# Diver_Board_V1_0.net
KiCad netlist of a schematic drawn in Altium Designer
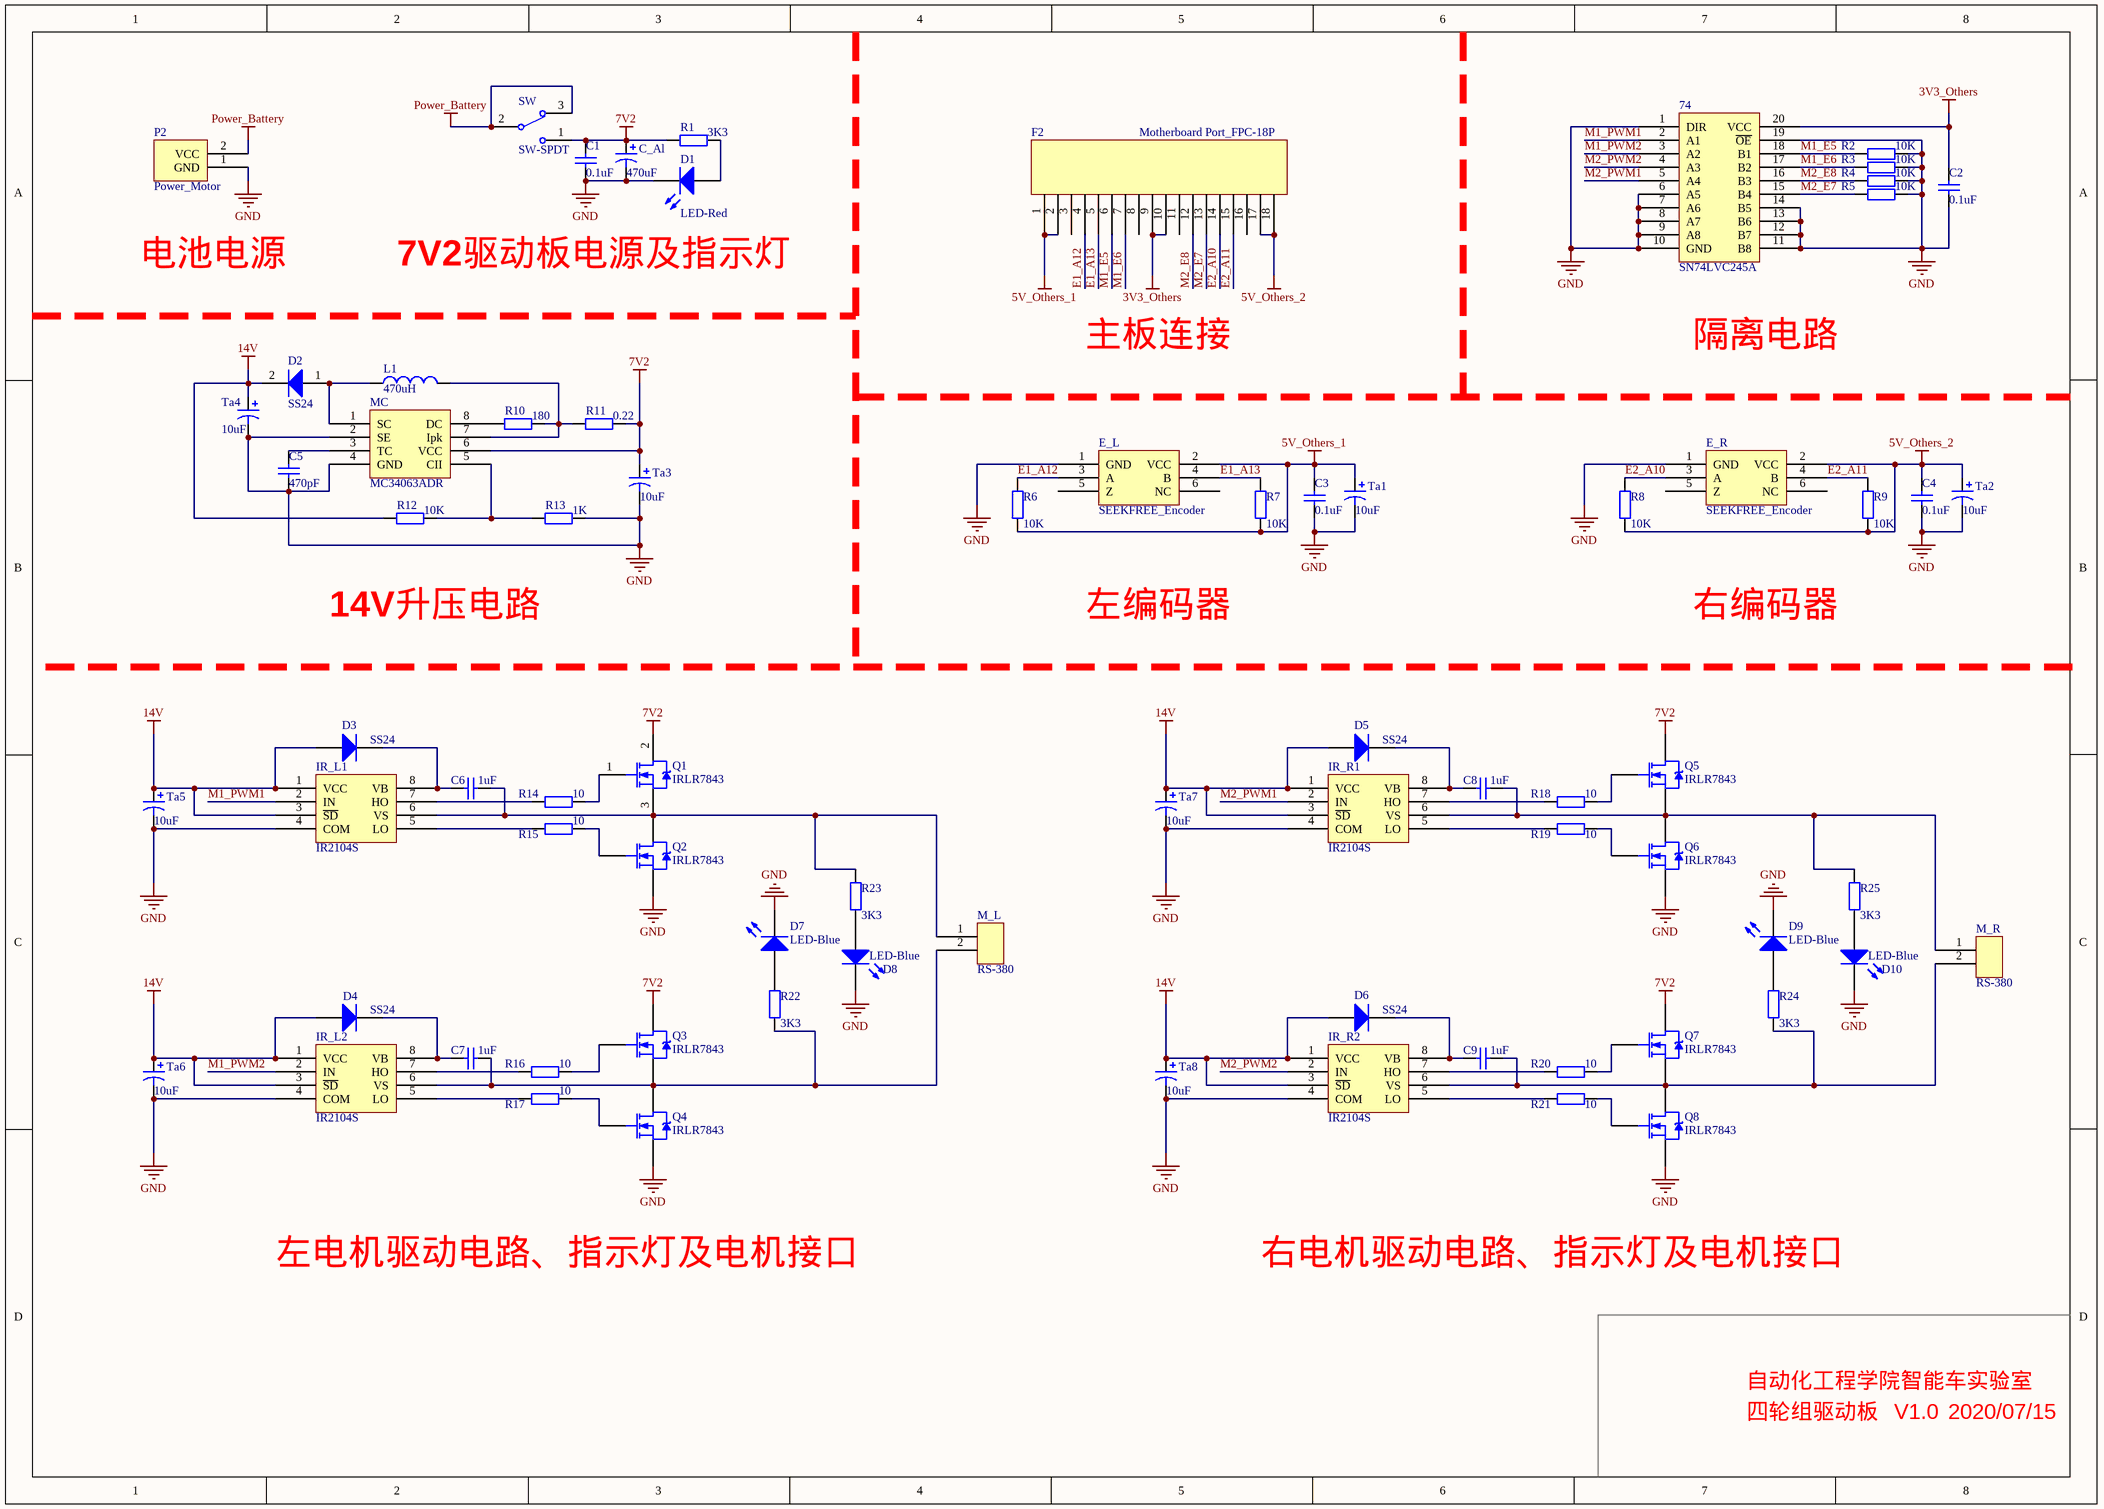
[diagram p0: Diver Board V1.0.SchDoc]

(export (version "E")
  (design (tool "Eeschema 10.0.6"))
  (components
    (comp (ref "74")
      (value "SN74LVC245A")
      (footprint "74LVC245_SOIC20")
      (libsource (lib "Diver Board V1.0") (part "74LVC245"))
    )
    (comp (ref "C1")
      (value "0.1uF")
      (footprint "C_0603")
      (description "Capacitor")
      (fields (field (name "PUBLISHER") "Altium Limited"))
      (libsource (lib "Miscellaneous Devices") (part "Cap"))
    )
    (comp (ref "C2")
      (value "0.1uF")
      (footprint "C_0603")
      (description "Capacitor")
      (fields (field (name "PUBLISHER") "Altium Limited"))
      (libsource (lib "Miscellaneous Devices") (part "Cap"))
    )
    (comp (ref "C3")
      (value "0.1uF")
      (footprint "C_0603")
      (description "Capacitor")
      (fields (field (name "PUBLISHER") "Altium Limited"))
      (libsource (lib "Miscellaneous Devices") (part "Cap"))
    )
    (comp (ref "C4")
      (value "0.1uF")
      (footprint "C_0603")
      (description "Capacitor")
      (fields (field (name "PUBLISHER") "Altium Limited"))
      (libsource (lib "Miscellaneous Devices") (part "Cap"))
    )
    (comp (ref "C5")
      (value "470pF")
      (footprint "C_0603")
      (description "Capacitor")
      (fields (field (name "PUBLISHER") "Altium Limited"))
      (libsource (lib "Miscellaneous Devices") (part "Cap"))
    )
    (comp (ref "C6")
      (value "1uF")
      (footprint "C_0603")
      (description "Capacitor")
      (fields (field (name "PUBLISHER") "Altium Limited"))
      (libsource (lib "Miscellaneous Devices") (part "Cap"))
    )
    (comp (ref "C7")
      (value "1uF")
      (footprint "C_0603")
      (description "Capacitor")
      (fields (field (name "PUBLISHER") "Altium Limited"))
      (libsource (lib "Miscellaneous Devices") (part "Cap"))
    )
    (comp (ref "C8")
      (value "1uF")
      (footprint "C_0603")
      (description "Capacitor")
      (fields (field (name "PUBLISHER") "Altium Limited"))
      (libsource (lib "Miscellaneous Devices") (part "Cap"))
    )
    (comp (ref "C9")
      (value "1uF")
      (footprint "C_0603")
      (description "Capacitor")
      (fields (field (name "PUBLISHER") "Altium Limited"))
      (libsource (lib "Miscellaneous Devices") (part "Cap"))
    )
    (comp (ref "C_Al")
      (value "470uF")
      (footprint "C_Al_8*11.5mm")
      (description "Polarized Capacitor (Surface Mount)")
      (fields (field (name "PUBLISHER") "Altium Limited"))
      (libsource (lib "Miscellaneous Devices") (part "Cap Pol3"))
    )
    (comp (ref "D1")
      (value "LED-Red")
      (footprint "LED_0603_R")
      (description "Typical BLUE SiC LED")
      (fields (field (name "PUBLISHER") "Altium Limited"))
      (libsource (lib "Miscellaneous Devices") (part "LED3"))
    )
    (comp (ref "D2")
      (value "SS24")
      (footprint "SS24_SMA")
      (description "Default Diode")
      (fields (field (name "PUBLISHER") "Altium Limited"))
      (libsource (lib "") (part "Diode_1"))
    )
    (comp (ref "D3")
      (value "SS24")
      (footprint "SS24_SMA")
      (description "Default Diode")
      (fields (field (name "PUBLISHER") "Altium Limited"))
      (libsource (lib "Miscellaneous Devices") (part "Diode"))
    )
    (comp (ref "D4")
      (value "SS24")
      (footprint "SS24_SMA")
      (description "Default Diode")
      (fields (field (name "PUBLISHER") "Altium Limited"))
      (libsource (lib "Miscellaneous Devices") (part "Diode"))
    )
    (comp (ref "D5")
      (value "SS24")
      (footprint "SS24_SMA")
      (description "Default Diode")
      (fields (field (name "PUBLISHER") "Altium Limited"))
      (libsource (lib "Miscellaneous Devices") (part "Diode"))
    )
    (comp (ref "D6")
      (value "SS24")
      (footprint "SS24_SMA")
      (description "Default Diode")
      (fields (field (name "PUBLISHER") "Altium Limited"))
      (libsource (lib "Miscellaneous Devices") (part "Diode"))
    )
    (comp (ref "D7")
      (value "LED-Blue")
      (footprint "LED_0603_B")
      (description "Typical BLUE SiC LED")
      (fields (field (name "PUBLISHER") "Altium Limited"))
      (libsource (lib "Miscellaneous Devices") (part "LED3"))
    )
    (comp (ref "D8")
      (value "LED-Blue")
      (footprint "LED_0603_B")
      (description "Typical BLUE SiC LED")
      (fields (field (name "PUBLISHER") "Altium Limited"))
      (libsource (lib "Miscellaneous Devices") (part "LED3"))
    )
    (comp (ref "D9")
      (value "LED-Blue")
      (footprint "LED_0603_B")
      (description "Typical BLUE SiC LED")
      (fields (field (name "PUBLISHER") "Altium Limited"))
      (libsource (lib "Miscellaneous Devices") (part "LED3"))
    )
    (comp (ref "D10")
      (value "LED-Blue")
      (footprint "LED_0603_B")
      (description "Typical BLUE SiC LED")
      (fields (field (name "PUBLISHER") "Altium Limited"))
      (libsource (lib "Miscellaneous Devices") (part "LED3"))
    )
    (comp (ref "E_L")
      (value "SEEKFREE_Encoder")
      (footprint "Encoder_L_2.54mm")
      (libsource (lib "Diver Board V1.0") (part "SEEKFREE_Encoder"))
    )
    (comp (ref "E_R")
      (value "SEEKFREE_Encoder")
      (footprint "Encoder_R_2.54mm")
      (libsource (lib "Diver Board V1.0") (part "SEEKFREE_Encoder"))
    )
    (comp (ref "F2")
      (value "Motherboard Port_FPC-18P")
      (footprint "Motherboard Port_0.5mm")
      (libsource (lib "Diver Board V1.0") (part "Motherboard Port"))
    )
    (comp (ref "IR_L1")
      (value "IR2104S")
      (footprint "IR2104_SOIC8")
      (libsource (lib "Diver Board V1.0") (part "IR2104"))
    )
    (comp (ref "IR_L2")
      (value "IR2104S")
      (footprint "IR2104_SOIC8")
      (libsource (lib "Diver Board V1.0") (part "IR2104"))
    )
    (comp (ref "IR_R1")
      (value "IR2104S")
      (footprint "IR2104_SOIC8")
      (libsource (lib "Diver Board V1.0") (part "IR2104"))
    )
    (comp (ref "IR_R2")
      (value "IR2104S")
      (footprint "IR2104_SOIC8")
      (libsource (lib "Diver Board V1.0") (part "IR2104"))
    )
    (comp (ref "L1")
      (value "470uH")
      (footprint "L_12.5*12.5mm")
      (description "Inductor")
      (fields (field (name "PUBLISHER") "Altium Limited"))
      (libsource (lib "Miscellaneous Devices") (part "Inductor"))
    )
    (comp (ref "MC")
      (value "MC34063ADR")
      (footprint "MC34063_SOIC8")
      (libsource (lib "Diver Board V1.0") (part "MC34063"))
    )
    (comp (ref "M_L")
      (value "RS-380")
      (footprint "Motor_4.7mm")
      (libsource (lib "Diver Board V1.0") (part "Motor Port"))
    )
    (comp (ref "M_R")
      (value "RS-380")
      (footprint "Motor_4.7mm")
      (libsource (lib "Diver Board V1.0") (part "Motor Port"))
    )
    (comp (ref "P2")
      (value "Power_Motor")
      (footprint "Battery_5mm")
      (libsource (lib "Diver Board V1.0") (part "Power_Motor"))
    )
    (comp (ref "Q1")
      (value "IRLR7843")
      (footprint "IRLR7843_TO-252")
      (description "N-Channel Power MOSFET")
      (fields (field (name "PUBLISHER") "Altium Limited"))
      (libsource (lib "") (part "NMOS-2_1"))
    )
    (comp (ref "Q2")
      (value "IRLR7843")
      (footprint "IRLR7843_TO-252")
      (description "N-Channel Power MOSFET")
      (fields (field (name "PUBLISHER") "Altium Limited"))
      (libsource (lib "Miscellaneous Devices") (part "NMOS-2"))
    )
    (comp (ref "Q3")
      (value "IRLR7843")
      (footprint "IRLR7843_TO-252")
      (description "N-Channel Power MOSFET")
      (fields (field (name "PUBLISHER") "Altium Limited"))
      (libsource (lib "Miscellaneous Devices") (part "NMOS-2"))
    )
    (comp (ref "Q4")
      (value "IRLR7843")
      (footprint "IRLR7843_TO-252")
      (description "N-Channel Power MOSFET")
      (fields (field (name "PUBLISHER") "Altium Limited"))
      (libsource (lib "Miscellaneous Devices") (part "NMOS-2"))
    )
    (comp (ref "Q5")
      (value "IRLR7843")
      (footprint "IRLR7843_TO-252")
      (description "N-Channel Power MOSFET")
      (fields (field (name "PUBLISHER") "Altium Limited"))
      (libsource (lib "Miscellaneous Devices") (part "NMOS-2"))
    )
    (comp (ref "Q6")
      (value "IRLR7843")
      (footprint "IRLR7843_TO-252")
      (description "N-Channel Power MOSFET")
      (fields (field (name "PUBLISHER") "Altium Limited"))
      (libsource (lib "Miscellaneous Devices") (part "NMOS-2"))
    )
    (comp (ref "Q7")
      (value "IRLR7843")
      (footprint "IRLR7843_TO-252")
      (description "N-Channel Power MOSFET")
      (fields (field (name "PUBLISHER") "Altium Limited"))
      (libsource (lib "Miscellaneous Devices") (part "NMOS-2"))
    )
    (comp (ref "Q8")
      (value "IRLR7843")
      (footprint "IRLR7843_TO-252")
      (description "N-Channel Power MOSFET")
      (fields (field (name "PUBLISHER") "Altium Limited"))
      (libsource (lib "Miscellaneous Devices") (part "NMOS-2"))
    )
    (comp (ref "R1")
      (value "3K3")
      (footprint "R_0603")
      (description "Resistor")
      (fields (field (name "PUBLISHER") "Altium Limited"))
      (libsource (lib "Miscellaneous Devices") (part "Res2"))
    )
    (comp (ref "R2")
      (value "10K")
      (footprint "R_0603")
      (description "Resistor")
      (fields (field (name "PUBLISHER") "Altium Limited"))
      (libsource (lib "Miscellaneous Devices") (part "Res2"))
    )
    (comp (ref "R3")
      (value "10K")
      (footprint "R_0603")
      (description "Resistor")
      (fields (field (name "PUBLISHER") "Altium Limited"))
      (libsource (lib "Miscellaneous Devices") (part "Res2"))
    )
    (comp (ref "R4")
      (value "10K")
      (footprint "R_0603")
      (description "Resistor")
      (fields (field (name "PUBLISHER") "Altium Limited"))
      (libsource (lib "Miscellaneous Devices") (part "Res2"))
    )
    (comp (ref "R5")
      (value "10K")
      (footprint "R_0603")
      (description "Resistor")
      (fields (field (name "PUBLISHER") "Altium Limited"))
      (libsource (lib "Miscellaneous Devices") (part "Res2"))
    )
    (comp (ref "R6")
      (value "10K")
      (footprint "R_0603")
      (description "Resistor")
      (fields (field (name "PUBLISHER") "Altium Limited"))
      (libsource (lib "") (part "Res2_1"))
    )
    (comp (ref "R7")
      (value "10K")
      (footprint "R_0603")
      (description "Resistor")
      (fields (field (name "PUBLISHER") "Altium Limited"))
      (libsource (lib "") (part "Res2_1"))
    )
    (comp (ref "R8")
      (value "10K")
      (footprint "R_0603")
      (description "Resistor")
      (fields (field (name "PUBLISHER") "Altium Limited"))
      (libsource (lib "") (part "Res2_1"))
    )
    (comp (ref "R9")
      (value "10K")
      (footprint "R_0603")
      (description "Resistor")
      (fields (field (name "PUBLISHER") "Altium Limited"))
      (libsource (lib "") (part "Res2_1"))
    )
    (comp (ref "R10")
      (value "180")
      (footprint "R_0603")
      (description "Resistor")
      (fields (field (name "PUBLISHER") "Altium Limited"))
      (libsource (lib "Miscellaneous Devices") (part "Res2"))
    )
    (comp (ref "R11")
      (value "0.22")
      (footprint "R_0603")
      (description "Resistor")
      (fields (field (name "PUBLISHER") "Altium Limited"))
      (libsource (lib "Miscellaneous Devices") (part "Res2"))
    )
    (comp (ref "R12")
      (value "10K")
      (footprint "R_0603")
      (description "Resistor")
      (fields (field (name "PUBLISHER") "Altium Limited"))
      (libsource (lib "Miscellaneous Devices") (part "Res2"))
    )
    (comp (ref "R13")
      (value "1K")
      (footprint "R_0603")
      (description "Resistor")
      (fields (field (name "PUBLISHER") "Altium Limited"))
      (libsource (lib "Miscellaneous Devices") (part "Res2"))
    )
    (comp (ref "R14")
      (value "10")
      (footprint "R_0603")
      (description "Resistor")
      (fields (field (name "PUBLISHER") "Altium Limited"))
      (libsource (lib "Miscellaneous Devices") (part "Res2"))
    )
    (comp (ref "R15")
      (value "10")
      (footprint "R_0603")
      (description "Resistor")
      (fields (field (name "PUBLISHER") "Altium Limited"))
      (libsource (lib "Miscellaneous Devices") (part "Res2"))
    )
    (comp (ref "R16")
      (value "10")
      (footprint "R_0603")
      (description "Resistor")
      (fields (field (name "PUBLISHER") "Altium Limited"))
      (libsource (lib "Miscellaneous Devices") (part "Res2"))
    )
    (comp (ref "R17")
      (value "10")
      (footprint "R_0603")
      (description "Resistor")
      (fields (field (name "PUBLISHER") "Altium Limited"))
      (libsource (lib "Miscellaneous Devices") (part "Res2"))
    )
    (comp (ref "R18")
      (value "10")
      (footprint "R_0603")
      (description "Resistor")
      (fields (field (name "PUBLISHER") "Altium Limited"))
      (libsource (lib "Miscellaneous Devices") (part "Res2"))
    )
    (comp (ref "R19")
      (value "10")
      (footprint "R_0603")
      (description "Resistor")
      (fields (field (name "PUBLISHER") "Altium Limited"))
      (libsource (lib "Miscellaneous Devices") (part "Res2"))
    )
    (comp (ref "R20")
      (value "10")
      (footprint "R_0603")
      (description "Resistor")
      (fields (field (name "PUBLISHER") "Altium Limited"))
      (libsource (lib "Miscellaneous Devices") (part "Res2"))
    )
    (comp (ref "R21")
      (value "10")
      (footprint "R_0603")
      (description "Resistor")
      (fields (field (name "PUBLISHER") "Altium Limited"))
      (libsource (lib "Miscellaneous Devices") (part "Res2"))
    )
    (comp (ref "R22")
      (value "3K3")
      (footprint "R_0603")
      (description "Resistor")
      (fields (field (name "PUBLISHER") "Altium Limited"))
      (libsource (lib "") (part "Res2_1"))
    )
    (comp (ref "R23")
      (value "3K3")
      (footprint "R_0603")
      (description "Resistor")
      (fields (field (name "PUBLISHER") "Altium Limited"))
      (libsource (lib "") (part "Res2_1"))
    )
    (comp (ref "R24")
      (value "3K3")
      (footprint "R_0603")
      (description "Resistor")
      (fields (field (name "PUBLISHER") "Altium Limited"))
      (libsource (lib "") (part "Res2_1"))
    )
    (comp (ref "R25")
      (value "3K3")
      (footprint "R_0603")
      (description "Resistor")
      (fields (field (name "PUBLISHER") "Altium Limited"))
      (libsource (lib "") (part "Res2_1"))
    )
    (comp (ref "SW")
      (value "SW-SPDT")
      (footprint "SW_4.7mm")
      (libsource (lib "Diver Board V1.0") (part "SW-SPDT"))
    )
    (comp (ref "Ta1")
      (value "10uF")
      (footprint "C_Ta_3528B")
      (description "Polarized Capacitor (Surface Mount)")
      (fields (field (name "PUBLISHER") "Altium Limited"))
      (libsource (lib "Miscellaneous Devices") (part "Cap Pol3"))
    )
    (comp (ref "Ta2")
      (value "10uF")
      (footprint "C_Ta_3528B")
      (description "Polarized Capacitor (Surface Mount)")
      (fields (field (name "PUBLISHER") "Altium Limited"))
      (libsource (lib "Miscellaneous Devices") (part "Cap Pol3"))
    )
    (comp (ref "Ta3")
      (value "10uF")
      (footprint "C_Ta_3528B")
      (description "Polarized Capacitor (Surface Mount)")
      (fields (field (name "PUBLISHER") "Altium Limited"))
      (libsource (lib "Miscellaneous Devices") (part "Cap Pol3"))
    )
    (comp (ref "Ta4")
      (value "10uF")
      (footprint "C_Ta_6032C")
      (description "Polarized Capacitor (Surface Mount)")
      (fields (field (name "PUBLISHER") "Altium Limited"))
      (libsource (lib "Miscellaneous Devices") (part "Cap Pol3"))
    )
    (comp (ref "Ta5")
      (value "10uF")
      (footprint "C_Ta_6032C")
      (description "Polarized Capacitor (Surface Mount)")
      (fields (field (name "PUBLISHER") "Altium Limited"))
      (libsource (lib "Miscellaneous Devices") (part "Cap Pol3"))
    )
    (comp (ref "Ta6")
      (value "10uF")
      (footprint "C_Ta_6032C")
      (description "Polarized Capacitor (Surface Mount)")
      (fields (field (name "PUBLISHER") "Altium Limited"))
      (libsource (lib "Miscellaneous Devices") (part "Cap Pol3"))
    )
    (comp (ref "Ta7")
      (value "10uF")
      (footprint "C_Ta_6032C")
      (description "Polarized Capacitor (Surface Mount)")
      (fields (field (name "PUBLISHER") "Altium Limited"))
      (libsource (lib "Miscellaneous Devices") (part "Cap Pol3"))
    )
    (comp (ref "Ta8")
      (value "10uF")
      (footprint "C_Ta_6032C")
      (description "Polarized Capacitor (Surface Mount)")
      (fields (field (name "PUBLISHER") "Altium Limited"))
      (libsource (lib "Miscellaneous Devices") (part "Cap Pol3"))
    )
  )
  (nets
    (net (code "1") (name "/E1_A12") (class "Default")
      (node (ref "E_L") (pin "3") (pinfunction "A_3") (pintype "passive"))
      (node (ref "F2") (pin "4") (pintype "passive"))
      (node (ref "R6") (pin "2") (pinfunction "2_2") (pintype "passive"))
    )
    (net (code "2") (name "/E1_A13") (class "Default")
      (node (ref "E_L") (pin "4") (pinfunction "B_4") (pintype "passive"))
      (node (ref "F2") (pin "5") (pintype "passive"))
      (node (ref "R7") (pin "2") (pinfunction "2_2") (pintype "passive"))
    )
    (net (code "3") (name "/E2_A10") (class "Default")
      (node (ref "E_R") (pin "3") (pinfunction "A_3") (pintype "passive"))
      (node (ref "F2") (pin "14") (pintype "passive"))
      (node (ref "R8") (pin "2") (pinfunction "2_2") (pintype "passive"))
    )
    (net (code "4") (name "/E2_A11") (class "Default")
      (node (ref "E_R") (pin "4") (pinfunction "B_4") (pintype "passive"))
      (node (ref "F2") (pin "15") (pintype "passive"))
      (node (ref "R9") (pin "2") (pinfunction "2_2") (pintype "passive"))
    )
    (net (code "5") (name "/M1_E5") (class "Default")
      (node (ref "74") (pin "18") (pinfunction "B1_18") (pintype "passive"))
      (node (ref "F2") (pin "6") (pintype "passive"))
      (node (ref "R2") (pin "1") (pinfunction "1_1") (pintype "passive"))
    )
    (net (code "6") (name "/M1_E6") (class "Default")
      (node (ref "74") (pin "17") (pinfunction "B2_17") (pintype "passive"))
      (node (ref "F2") (pin "7") (pintype "passive"))
      (node (ref "R3") (pin "1") (pinfunction "1_1") (pintype "passive"))
    )
    (net (code "7") (name "/M1_PWM1") (class "Default")
      (node (ref "74") (pin "2") (pinfunction "A1_2") (pintype "passive"))
      (node (ref "IR_L1") (pin "2") (pinfunction "IN_2") (pintype "passive"))
    )
    (net (code "8") (name "/M1_PWM2") (class "Default")
      (node (ref "74") (pin "3") (pinfunction "A2_3") (pintype "passive"))
      (node (ref "IR_L2") (pin "2") (pinfunction "IN_2") (pintype "passive"))
    )
    (net (code "9") (name "/M2_E7") (class "Default")
      (node (ref "74") (pin "15") (pinfunction "B4_15") (pintype "passive"))
      (node (ref "F2") (pin "13") (pintype "passive"))
      (node (ref "R5") (pin "1") (pinfunction "1_1") (pintype "passive"))
    )
    (net (code "10") (name "/M2_E8") (class "Default")
      (node (ref "74") (pin "16") (pinfunction "B3_16") (pintype "passive"))
      (node (ref "F2") (pin "12") (pintype "passive"))
      (node (ref "R4") (pin "1") (pinfunction "1_1") (pintype "passive"))
    )
    (net (code "11") (name "/M2_PWM1") (class "Default")
      (node (ref "74") (pin "5") (pinfunction "A4_5") (pintype "passive"))
      (node (ref "IR_R1") (pin "2") (pinfunction "IN_2") (pintype "passive"))
    )
    (net (code "12") (name "/M2_PWM2") (class "Default")
      (node (ref "74") (pin "4") (pinfunction "A3_4") (pintype "passive"))
      (node (ref "IR_R2") (pin "2") (pinfunction "IN_2") (pintype "passive"))
    )
    (net (code "13") (name "3V3_Others") (class "Default")
      (node (ref "74") (pin "20") (pinfunction "VCC_20") (pintype "passive"))
      (node (ref "C2") (pin "2") (pinfunction "2_2") (pintype "passive"))
      (node (ref "F2") (pin "10") (pintype "passive"))
      (node (ref "F2") (pin "9") (pintype "passive"))
    )
    (net (code "14") (name "5V_Others_1") (class "Default")
      (node (ref "C3") (pin "2") (pinfunction "2_2") (pintype "passive"))
      (node (ref "E_L") (pin "2") (pinfunction "VCC_2") (pintype "passive"))
      (node (ref "F2") (pin "1") (pintype "passive"))
      (node (ref "F2") (pin "2") (pintype "passive"))
      (node (ref "R6") (pin "1") (pinfunction "1_1") (pintype "passive"))
      (node (ref "R7") (pin "1") (pinfunction "1_1") (pintype "passive"))
      (node (ref "Ta1") (pin "1") (pinfunction "1_1") (pintype "passive"))
    )
    (net (code "15") (name "5V_Others_2") (class "Default")
      (node (ref "C4") (pin "2") (pinfunction "2_2") (pintype "passive"))
      (node (ref "E_R") (pin "2") (pinfunction "VCC_2") (pintype "passive"))
      (node (ref "F2") (pin "17") (pintype "passive"))
      (node (ref "F2") (pin "18") (pintype "passive"))
      (node (ref "R8") (pin "1") (pinfunction "1_1") (pintype "passive"))
      (node (ref "R9") (pin "1") (pinfunction "1_1") (pintype "passive"))
      (node (ref "Ta2") (pin "1") (pinfunction "1_1") (pintype "passive"))
    )
    (net (code "16") (name "7V2") (class "Default")
      (node (ref "C1") (pin "2") (pinfunction "2_2") (pintype "passive"))
      (node (ref "C_Al") (pin "1") (pinfunction "1_1") (pintype "passive"))
      (node (ref "MC") (pin "6") (pinfunction "VCC_6") (pintype "passive"))
      (node (ref "Q1") (pin "2") (pinfunction "D_2") (pintype "passive"))
      (node (ref "Q3") (pin "2") (pinfunction "D_2") (pintype "passive"))
      (node (ref "Q5") (pin "2") (pinfunction "D_2") (pintype "passive"))
      (node (ref "Q7") (pin "2") (pinfunction "D_2") (pintype "passive"))
      (node (ref "R1") (pin "1") (pinfunction "1_1") (pintype "passive"))
      (node (ref "R11") (pin "2") (pinfunction "2_2") (pintype "passive"))
      (node (ref "SW") (pin "1") (pintype "passive"))
      (node (ref "Ta3") (pin "1") (pinfunction "1_1") (pintype "passive"))
    )
    (net (code "17") (name "14V") (class "Default")
      (node (ref "D2") (pin "2") (pinfunction "K_2") (pintype "passive"))
      (node (ref "D3") (pin "1") (pinfunction "A_1") (pintype "passive"))
      (node (ref "D4") (pin "1") (pinfunction "A_1") (pintype "passive"))
      (node (ref "D5") (pin "1") (pinfunction "A_1") (pintype "passive"))
      (node (ref "D6") (pin "1") (pinfunction "A_1") (pintype "passive"))
      (node (ref "IR_L1") (pin "1") (pinfunction "VCC_1") (pintype "passive"))
      (node (ref "IR_L1") (pin "3") (pinfunction "~{SD}_3") (pintype "passive"))
      (node (ref "IR_L2") (pin "1") (pinfunction "VCC_1") (pintype "passive"))
      (node (ref "IR_L2") (pin "3") (pinfunction "~{SD}_3") (pintype "passive"))
      (node (ref "IR_R1") (pin "1") (pinfunction "VCC_1") (pintype "passive"))
      (node (ref "IR_R1") (pin "3") (pinfunction "~{SD}_3") (pintype "passive"))
      (node (ref "IR_R2") (pin "1") (pinfunction "VCC_1") (pintype "passive"))
      (node (ref "IR_R2") (pin "3") (pinfunction "~{SD}_3") (pintype "passive"))
      (node (ref "R12") (pin "1") (pinfunction "1_1") (pintype "passive"))
      (node (ref "Ta4") (pin "1") (pinfunction "1_1") (pintype "passive"))
      (node (ref "Ta5") (pin "1") (pinfunction "1_1") (pintype "passive"))
      (node (ref "Ta6") (pin "1") (pinfunction "1_1") (pintype "passive"))
      (node (ref "Ta7") (pin "1") (pinfunction "1_1") (pintype "passive"))
      (node (ref "Ta8") (pin "1") (pinfunction "1_1") (pintype "passive"))
    )
    (net (code "18") (name "GND") (class "Default")
      (node (ref "74") (pin "1") (pinfunction "DIR_1") (pintype "passive"))
      (node (ref "74") (pin "10") (pinfunction "GND_10") (pintype "passive"))
      (node (ref "74") (pin "11") (pinfunction "B8_11") (pintype "passive"))
      (node (ref "74") (pin "12") (pinfunction "B7_12") (pintype "passive"))
      (node (ref "74") (pin "13") (pinfunction "B6_13") (pintype "passive"))
      (node (ref "74") (pin "14") (pinfunction "B5_14") (pintype "passive"))
      (node (ref "74") (pin "19") (pinfunction "~{OE}_19") (pintype "passive"))
      (node (ref "74") (pin "6") (pinfunction "A5_6") (pintype "passive"))
      (node (ref "74") (pin "7") (pinfunction "A6_7") (pintype "passive"))
      (node (ref "74") (pin "8") (pinfunction "A7_8") (pintype "passive"))
      (node (ref "74") (pin "9") (pinfunction "A8_9") (pintype "passive"))
      (node (ref "C1") (pin "1") (pinfunction "1_1") (pintype "passive"))
      (node (ref "C2") (pin "1") (pinfunction "1_1") (pintype "passive"))
      (node (ref "C3") (pin "1") (pinfunction "1_1") (pintype "passive"))
      (node (ref "C4") (pin "1") (pinfunction "1_1") (pintype "passive"))
      (node (ref "C5") (pin "2") (pinfunction "2_2") (pintype "passive"))
      (node (ref "C_Al") (pin "2") (pinfunction "2_2") (pintype "passive"))
      (node (ref "D1") (pin "2") (pinfunction "K_2") (pintype "passive"))
      (node (ref "D10") (pin "2") (pinfunction "K_2") (pintype "passive"))
      (node (ref "D7") (pin "2") (pinfunction "K_2") (pintype "passive"))
      (node (ref "D8") (pin "2") (pinfunction "K_2") (pintype "passive"))
      (node (ref "D9") (pin "2") (pinfunction "K_2") (pintype "passive"))
      (node (ref "E_L") (pin "1") (pinfunction "GND_1") (pintype "passive"))
      (node (ref "E_R") (pin "1") (pinfunction "GND_1") (pintype "passive"))
      (node (ref "IR_L1") (pin "4") (pinfunction "COM_4") (pintype "passive"))
      (node (ref "IR_L2") (pin "4") (pinfunction "COM_4") (pintype "passive"))
      (node (ref "IR_R1") (pin "4") (pinfunction "COM_4") (pintype "passive"))
      (node (ref "IR_R2") (pin "4") (pinfunction "COM_4") (pintype "passive"))
      (node (ref "MC") (pin "2") (pinfunction "SE_2") (pintype "passive"))
      (node (ref "MC") (pin "4") (pinfunction "GND_4") (pintype "passive"))
      (node (ref "P2") (pin "1") (pinfunction "GND_1") (pintype "passive"))
      (node (ref "Q2") (pin "3") (pinfunction "S_3") (pintype "passive"))
      (node (ref "Q4") (pin "3") (pinfunction "S_3") (pintype "passive"))
      (node (ref "Q6") (pin "3") (pinfunction "S_3") (pintype "passive"))
      (node (ref "Q8") (pin "3") (pinfunction "S_3") (pintype "passive"))
      (node (ref "R13") (pin "2") (pinfunction "2_2") (pintype "passive"))
      (node (ref "R2") (pin "2") (pinfunction "2_2") (pintype "passive"))
      (node (ref "R3") (pin "2") (pinfunction "2_2") (pintype "passive"))
      (node (ref "R4") (pin "2") (pinfunction "2_2") (pintype "passive"))
      (node (ref "R5") (pin "2") (pinfunction "2_2") (pintype "passive"))
      (node (ref "Ta1") (pin "2") (pinfunction "2_2") (pintype "passive"))
      (node (ref "Ta2") (pin "2") (pinfunction "2_2") (pintype "passive"))
      (node (ref "Ta3") (pin "2") (pinfunction "2_2") (pintype "passive"))
      (node (ref "Ta4") (pin "2") (pinfunction "2_2") (pintype "passive"))
      (node (ref "Ta5") (pin "2") (pinfunction "2_2") (pintype "passive"))
      (node (ref "Ta6") (pin "2") (pinfunction "2_2") (pintype "passive"))
      (node (ref "Ta7") (pin "2") (pinfunction "2_2") (pintype "passive"))
      (node (ref "Ta8") (pin "2") (pinfunction "2_2") (pintype "passive"))
    )
    (net (code "19") (name "Net-(D1-A)") (class "Default")
      (node (ref "D1") (pin "1") (pinfunction "A_1") (pintype "passive"))
      (node (ref "R1") (pin "2") (pinfunction "2_2") (pintype "passive"))
    )
    (net (code "20") (name "Net-(D2-A)") (class "Default")
      (node (ref "D2") (pin "1") (pinfunction "A_1") (pintype "passive"))
      (node (ref "L1") (pin "1") (pinfunction "1_1") (pintype "passive"))
      (node (ref "MC") (pin "1") (pinfunction "SC_1") (pintype "passive"))
    )
    (net (code "21") (name "Net-(D3-K)") (class "Default")
      (node (ref "C6") (pin "2") (pinfunction "2_2") (pintype "passive"))
      (node (ref "D3") (pin "2") (pinfunction "K_2") (pintype "passive"))
      (node (ref "IR_L1") (pin "8") (pinfunction "VB_8") (pintype "passive"))
    )
    (net (code "22") (name "Net-(D4-K)") (class "Default")
      (node (ref "C7") (pin "2") (pinfunction "2_2") (pintype "passive"))
      (node (ref "D4") (pin "2") (pinfunction "K_2") (pintype "passive"))
      (node (ref "IR_L2") (pin "8") (pinfunction "VB_8") (pintype "passive"))
    )
    (net (code "23") (name "Net-(D5-K)") (class "Default")
      (node (ref "C8") (pin "2") (pinfunction "2_2") (pintype "passive"))
      (node (ref "D5") (pin "2") (pinfunction "K_2") (pintype "passive"))
      (node (ref "IR_R1") (pin "8") (pinfunction "VB_8") (pintype "passive"))
    )
    (net (code "24") (name "Net-(D6-K)") (class "Default")
      (node (ref "C9") (pin "2") (pinfunction "2_2") (pintype "passive"))
      (node (ref "D6") (pin "2") (pinfunction "K_2") (pintype "passive"))
      (node (ref "IR_R2") (pin "8") (pinfunction "VB_8") (pintype "passive"))
    )
    (net (code "25") (name "Net-(D7-A)") (class "Default")
      (node (ref "D7") (pin "1") (pinfunction "A_1") (pintype "passive"))
      (node (ref "R22") (pin "2") (pinfunction "2_2") (pintype "passive"))
    )
    (net (code "26") (name "Net-(D8-A)") (class "Default")
      (node (ref "D8") (pin "1") (pinfunction "A_1") (pintype "passive"))
      (node (ref "R23") (pin "1") (pinfunction "1_1") (pintype "passive"))
    )
    (net (code "27") (name "Net-(D9-A)") (class "Default")
      (node (ref "D9") (pin "1") (pinfunction "A_1") (pintype "passive"))
      (node (ref "R24") (pin "2") (pinfunction "2_2") (pintype "passive"))
    )
    (net (code "28") (name "Net-(D10-A)") (class "Default")
      (node (ref "D10") (pin "1") (pinfunction "A_1") (pintype "passive"))
      (node (ref "R25") (pin "1") (pinfunction "1_1") (pintype "passive"))
    )
    (net (code "29") (name "Net-(IR_L1-HO)") (class "Default")
      (node (ref "IR_L1") (pin "7") (pinfunction "HO_7") (pintype "passive"))
      (node (ref "R14") (pin "1") (pinfunction "1_1") (pintype "passive"))
    )
    (net (code "30") (name "Net-(IR_L1-LO)") (class "Default")
      (node (ref "IR_L1") (pin "5") (pinfunction "LO_5") (pintype "passive"))
      (node (ref "R15") (pin "1") (pinfunction "1_1") (pintype "passive"))
    )
    (net (code "31") (name "Net-(IR_L1-VS)") (class "Default")
      (node (ref "C6") (pin "1") (pinfunction "1_1") (pintype "passive"))
      (node (ref "IR_L1") (pin "6") (pinfunction "VS_6") (pintype "passive"))
      (node (ref "M_L") (pin "1") (pintype "passive"))
      (node (ref "Q1") (pin "3") (pinfunction "S_3") (pintype "passive"))
      (node (ref "Q2") (pin "2") (pinfunction "D_2") (pintype "passive"))
      (node (ref "R23") (pin "2") (pinfunction "2_2") (pintype "passive"))
    )
    (net (code "32") (name "Net-(IR_L2-HO)") (class "Default")
      (node (ref "IR_L2") (pin "7") (pinfunction "HO_7") (pintype "passive"))
      (node (ref "R16") (pin "1") (pinfunction "1_1") (pintype "passive"))
    )
    (net (code "33") (name "Net-(IR_L2-LO)") (class "Default")
      (node (ref "IR_L2") (pin "5") (pinfunction "LO_5") (pintype "passive"))
      (node (ref "R17") (pin "1") (pinfunction "1_1") (pintype "passive"))
    )
    (net (code "34") (name "Net-(IR_L2-VS)") (class "Default")
      (node (ref "C7") (pin "1") (pinfunction "1_1") (pintype "passive"))
      (node (ref "IR_L2") (pin "6") (pinfunction "VS_6") (pintype "passive"))
      (node (ref "M_L") (pin "2") (pintype "passive"))
      (node (ref "Q3") (pin "3") (pinfunction "S_3") (pintype "passive"))
      (node (ref "Q4") (pin "2") (pinfunction "D_2") (pintype "passive"))
      (node (ref "R22") (pin "1") (pinfunction "1_1") (pintype "passive"))
    )
    (net (code "35") (name "Net-(IR_R1-HO)") (class "Default")
      (node (ref "IR_R1") (pin "7") (pinfunction "HO_7") (pintype "passive"))
      (node (ref "R18") (pin "1") (pinfunction "1_1") (pintype "passive"))
    )
    (net (code "36") (name "Net-(IR_R1-LO)") (class "Default")
      (node (ref "IR_R1") (pin "5") (pinfunction "LO_5") (pintype "passive"))
      (node (ref "R19") (pin "1") (pinfunction "1_1") (pintype "passive"))
    )
    (net (code "37") (name "Net-(IR_R1-VS)") (class "Default")
      (node (ref "C8") (pin "1") (pinfunction "1_1") (pintype "passive"))
      (node (ref "IR_R1") (pin "6") (pinfunction "VS_6") (pintype "passive"))
      (node (ref "M_R") (pin "1") (pintype "passive"))
      (node (ref "Q5") (pin "3") (pinfunction "S_3") (pintype "passive"))
      (node (ref "Q6") (pin "2") (pinfunction "D_2") (pintype "passive"))
      (node (ref "R25") (pin "2") (pinfunction "2_2") (pintype "passive"))
    )
    (net (code "38") (name "Net-(IR_R2-HO)") (class "Default")
      (node (ref "IR_R2") (pin "7") (pinfunction "HO_7") (pintype "passive"))
      (node (ref "R20") (pin "1") (pinfunction "1_1") (pintype "passive"))
    )
    (net (code "39") (name "Net-(IR_R2-LO)") (class "Default")
      (node (ref "IR_R2") (pin "5") (pinfunction "LO_5") (pintype "passive"))
      (node (ref "R21") (pin "1") (pinfunction "1_1") (pintype "passive"))
    )
    (net (code "40") (name "Net-(IR_R2-VS)") (class "Default")
      (node (ref "C9") (pin "1") (pinfunction "1_1") (pintype "passive"))
      (node (ref "IR_R2") (pin "6") (pinfunction "VS_6") (pintype "passive"))
      (node (ref "M_R") (pin "2") (pintype "passive"))
      (node (ref "Q7") (pin "3") (pinfunction "S_3") (pintype "passive"))
      (node (ref "Q8") (pin "2") (pinfunction "D_2") (pintype "passive"))
      (node (ref "R24") (pin "1") (pinfunction "1_1") (pintype "passive"))
    )
    (net (code "41") (name "Net-(MC-CII)") (class "Default")
      (node (ref "MC") (pin "5") (pinfunction "CII_5") (pintype "passive"))
      (node (ref "R12") (pin "2") (pinfunction "2_2") (pintype "passive"))
      (node (ref "R13") (pin "1") (pinfunction "1_1") (pintype "passive"))
    )
    (net (code "42") (name "Net-(MC-DC)") (class "Default")
      (node (ref "MC") (pin "8") (pinfunction "DC_8") (pintype "passive"))
      (node (ref "R10") (pin "1") (pinfunction "1_1") (pintype "passive"))
    )
    (net (code "43") (name "Net-(MC-Ipk)") (class "Default")
      (node (ref "L1") (pin "2") (pinfunction "2_2") (pintype "passive"))
      (node (ref "MC") (pin "7") (pinfunction "Ipk_7") (pintype "passive"))
      (node (ref "R10") (pin "2") (pinfunction "2_2") (pintype "passive"))
      (node (ref "R11") (pin "1") (pinfunction "1_1") (pintype "passive"))
    )
    (net (code "44") (name "Net-(MC-TC)") (class "Default")
      (node (ref "C5") (pin "1") (pinfunction "1_1") (pintype "passive"))
      (node (ref "MC") (pin "3") (pinfunction "TC_3") (pintype "passive"))
    )
    (net (code "45") (name "Net-(Q1-G)") (class "Default")
      (node (ref "Q1") (pin "1") (pinfunction "G_1") (pintype "passive"))
      (node (ref "R14") (pin "2") (pinfunction "2_2") (pintype "passive"))
    )
    (net (code "46") (name "Net-(Q2-G)") (class "Default")
      (node (ref "Q2") (pin "1") (pinfunction "G_1") (pintype "passive"))
      (node (ref "R15") (pin "2") (pinfunction "2_2") (pintype "passive"))
    )
    (net (code "47") (name "Net-(Q3-G)") (class "Default")
      (node (ref "Q3") (pin "1") (pinfunction "G_1") (pintype "passive"))
      (node (ref "R16") (pin "2") (pinfunction "2_2") (pintype "passive"))
    )
    (net (code "48") (name "Net-(Q4-G)") (class "Default")
      (node (ref "Q4") (pin "1") (pinfunction "G_1") (pintype "passive"))
      (node (ref "R17") (pin "2") (pinfunction "2_2") (pintype "passive"))
    )
    (net (code "49") (name "Net-(Q5-G)") (class "Default")
      (node (ref "Q5") (pin "1") (pinfunction "G_1") (pintype "passive"))
      (node (ref "R18") (pin "2") (pinfunction "2_2") (pintype "passive"))
    )
    (net (code "50") (name "Net-(Q6-G)") (class "Default")
      (node (ref "Q6") (pin "1") (pinfunction "G_1") (pintype "passive"))
      (node (ref "R19") (pin "2") (pinfunction "2_2") (pintype "passive"))
    )
    (net (code "51") (name "Net-(Q7-G)") (class "Default")
      (node (ref "Q7") (pin "1") (pinfunction "G_1") (pintype "passive"))
      (node (ref "R20") (pin "2") (pinfunction "2_2") (pintype "passive"))
    )
    (net (code "52") (name "Net-(Q8-G)") (class "Default")
      (node (ref "Q8") (pin "1") (pinfunction "G_1") (pintype "passive"))
      (node (ref "R21") (pin "2") (pinfunction "2_2") (pintype "passive"))
    )
    (net (code "53") (name "Power_Battery") (class "Default")
      (node (ref "P2") (pin "2") (pinfunction "VCC_2") (pintype "passive"))
      (node (ref "SW") (pin "2") (pintype "passive"))
      (node (ref "SW") (pin "3") (pintype "passive"))
    )
    (net (code "54") (name "unconnected-(E_L-NC-Pad6)") (class "Default")
      (node (ref "E_L") (pin "6") (pinfunction "NC_6") (pintype "passive"))
    )
    (net (code "55") (name "unconnected-(E_L-Z-Pad5)") (class "Default")
      (node (ref "E_L") (pin "5") (pinfunction "Z_5") (pintype "passive"))
    )
    (net (code "56") (name "unconnected-(E_R-NC-Pad6)") (class "Default")
      (node (ref "E_R") (pin "6") (pinfunction "NC_6") (pintype "passive"))
    )
    (net (code "57") (name "unconnected-(E_R-Z-Pad5)") (class "Default")
      (node (ref "E_R") (pin "5") (pinfunction "Z_5") (pintype "passive"))
    )
    (net (code "58") (name "unconnected-(F2-Pad3)") (class "Default")
      (node (ref "F2") (pin "3") (pintype "passive"))
    )
    (net (code "59") (name "unconnected-(F2-Pad8)") (class "Default")
      (node (ref "F2") (pin "8") (pintype "passive"))
    )
    (net (code "60") (name "unconnected-(F2-Pad11)") (class "Default")
      (node (ref "F2") (pin "11") (pintype "passive"))
    )
    (net (code "61") (name "unconnected-(F2-Pad16)") (class "Default")
      (node (ref "F2") (pin "16") (pintype "passive"))
    )
  )
)
